# GIO.net
KiCad netlist of a schematic drawn in Altium Designer
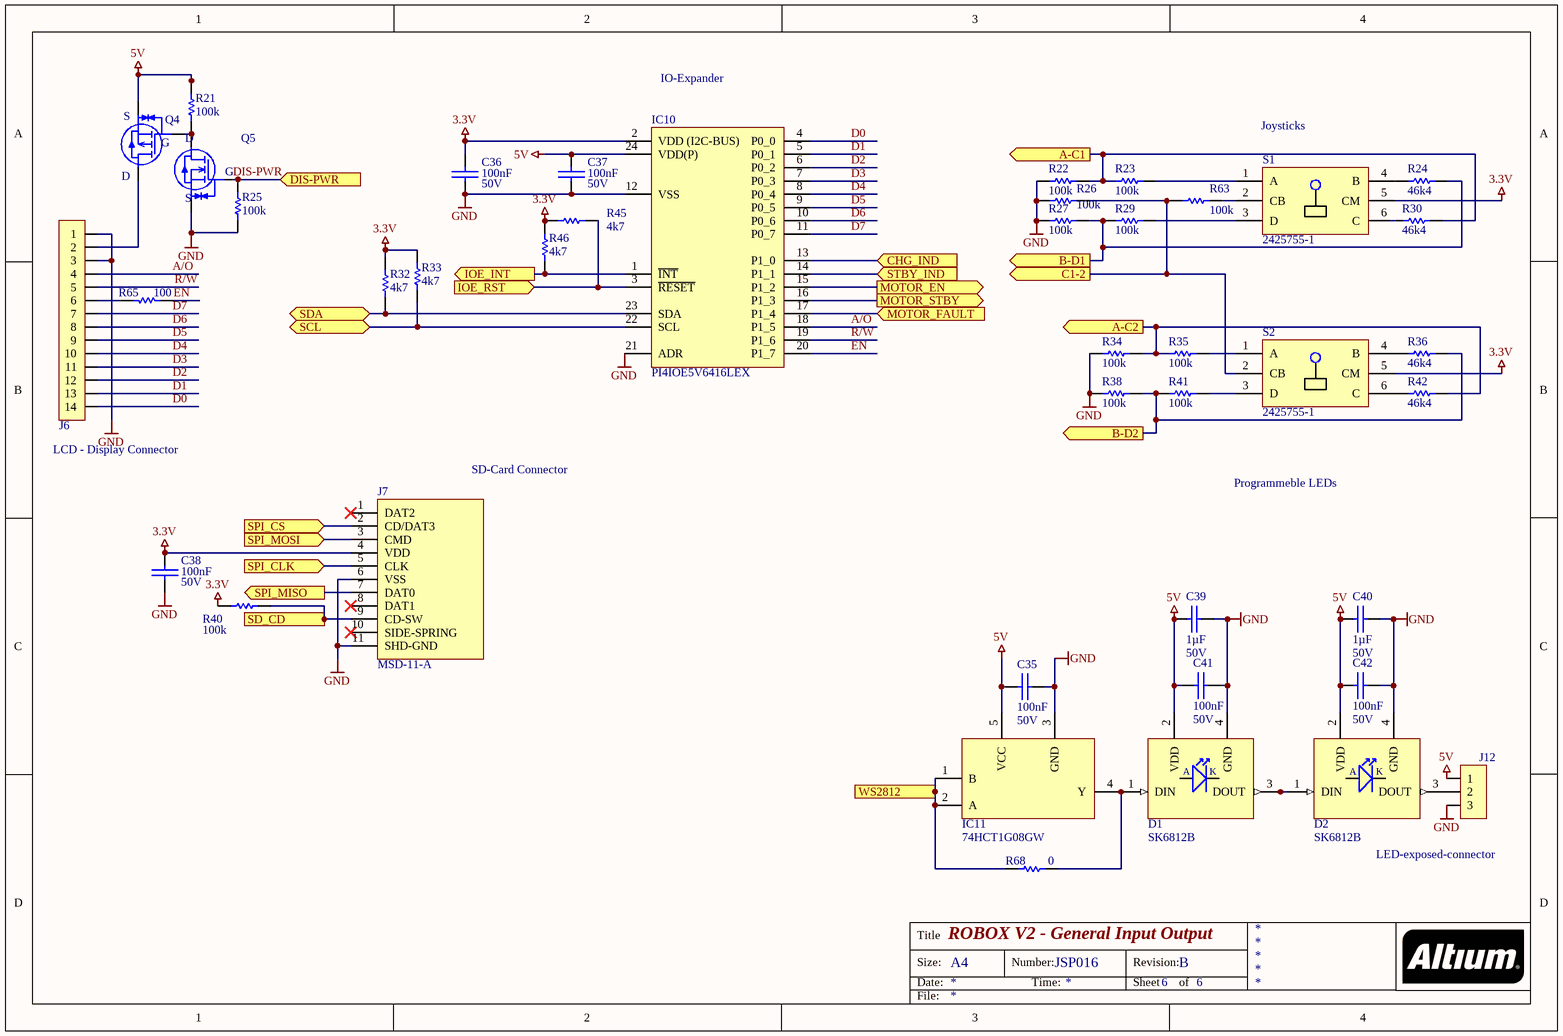
[diagram p0: GIO.SchDoc]

(export (version "E")
  (design (tool "Eeschema 10.0.6"))
  (components
    (comp (ref "C35")
      (value "100nF")
      (footprint "TH5.08")
      (description "CAP CER TH 100nF X7R 50V")
      (fields
        (field (name "MANUFACTURER") "FH")
        (field (name "TOLERANCE") "10%")
        (field (name "VOLTAGE") "50V")
      )
      (libsource (lib "bond-altium-excell") (part "cap_non_pol"))
    )
    (comp (ref "C36")
      (value "100nF")
      (footprint "C0402")
      (description "CAP CER 0.1UF 50V X5R 0402")
      (fields
        (field (name "MANUFACTURER") "Murata Electronics")
        (field (name "TOLERANCE") "5%")
        (field (name "VOLTAGE") "50V")
      )
      (libsource (lib "bond-altium-excell") (part "cap_non_pol"))
    )
    (comp (ref "C37")
      (value "100nF")
      (footprint "C0402")
      (description "CAP CER 0.1UF 50V X5R 0402")
      (fields
        (field (name "MANUFACTURER") "Murata Electronics")
        (field (name "TOLERANCE") "5%")
        (field (name "VOLTAGE") "50V")
      )
      (libsource (lib "bond-altium-excell") (part "cap_non_pol"))
    )
    (comp (ref "C38")
      (value "100nF")
      (footprint "C0402")
      (description "CAP CER 0.1UF 50V X5R 0402")
      (fields
        (field (name "MANUFACTURER") "Murata Electronics")
        (field (name "TOLERANCE") "5%")
        (field (name "VOLTAGE") "50V")
      )
      (libsource (lib "bond-altium-excell") (part "cap_non_pol"))
    )
    (comp (ref "C39")
      (value "1µF")
      (footprint "TH5.08")
      (description "CAP CER TH 1µF X7R 50V")
      (fields
        (field (name "MANUFACTURER") "Dersonic")
        (field (name "TOLERANCE") "20%")
        (field (name "VOLTAGE") "50V")
      )
      (libsource (lib "bond-altium-excell") (part "cap_non_pol"))
    )
    (comp (ref "C40")
      (value "1µF")
      (footprint "TH5.08")
      (description "CAP CER TH 1µF X7R 50V")
      (fields
        (field (name "MANUFACTURER") "Dersonic")
        (field (name "TOLERANCE") "20%")
        (field (name "VOLTAGE") "50V")
      )
      (libsource (lib "bond-altium-excell") (part "cap_non_pol"))
    )
    (comp (ref "C41")
      (value "100nF")
      (footprint "TH5.08")
      (description "CAP CER TH 100nF X7R 50V")
      (fields
        (field (name "MANUFACTURER") "FH")
        (field (name "TOLERANCE") "10%")
        (field (name "VOLTAGE") "50V")
      )
      (libsource (lib "bond-altium-excell") (part "cap_non_pol"))
    )
    (comp (ref "C42")
      (value "100nF")
      (footprint "TH5.08")
      (description "CAP CER TH 100nF X7R 50V")
      (fields
        (field (name "MANUFACTURER") "FH")
        (field (name "TOLERANCE") "10%")
        (field (name "VOLTAGE") "50V")
      )
      (libsource (lib "bond-altium-excell") (part "cap_non_pol"))
    )
    (comp (ref "D1")
      (value "SK6812B")
      (footprint "SK6812B")
      (description "ADDRESS LED DISCRETE RGB 4X2MM")
      (fields (field (name "MANUFACTURER") "Adafruit Industries LLC"))
      (libsource (lib "bond-altium-excell") (part "SK6812B"))
    )
    (comp (ref "D2")
      (value "SK6812B")
      (footprint "SK6812B")
      (description "ADDRESS LED DISCRETE RGB 4X2MM")
      (fields (field (name "MANUFACTURER") "Adafruit Industries LLC"))
      (libsource (lib "bond-altium-excell") (part "SK6812B"))
    )
    (comp (ref "IC10")
      (value "PI4IOE5V6416LEX")
      (footprint "TSSOP-24")
      (description "IC XPNDR 400KHZ I2C 24TSSOP")
      (fields (field (name "MANUFACTURER") "Diodes Incorporated"))
      (libsource (lib "bond-altium-excell") (part "PI4IOE5V6416LEX"))
    )
    (comp (ref "IC11")
      (value "74HCT1G08GW")
      (footprint "TSSOP-5")
      (description "IC GATE AND 1CH 2-INP 5TSSOP")
      (fields (field (name "MANUFACTURER") "Nexperia USA Inc."))
      (libsource (lib "bond-altium-excell") (part "74HCT1G08GW"))
    )
    (comp (ref "J6")
      (value "Pin-14")
      (footprint "HLW14S-2C7LF")
      (description "CONN FFC FPC VERT 14POS 1MM PCB")
      (fields (field (name "MANUFACTURER") "Amphenol ICC (FCI)"))
      (libsource (lib "bond-altium-excell") (part "Pin-14"))
    )
    (comp (ref "J7")
      (value "MSD-11-A")
      (footprint "MSD-11-A")
      (description "MICRO SD CARD CONNECTOR, 8 POSIT")
      (fields (field (name "MANUFACTURER") "CUI Devices"))
      (libsource (lib "bond-altium-excell") (part "MSD-11-A"))
    )
    (comp (ref "J12")
      (value "Pin-3")
      (footprint "3-PIN-EMPTY")
      (description "CONN TH solder pad")
      (libsource (lib "bond-altium-excell") (part "Pin-3"))
    )
    (comp (ref "Q4")
      (value "P_CH_MOSFET2")
      (footprint "SOT-323")
      (description "MOSFET P-CH 20V 820MA SOT323")
      (fields (field (name "MANUFACTURER") "Diodes Incorporated"))
      (libsource (lib "bond-altium-excell") (part "P_CH_MOSFET2"))
    )
    (comp (ref "Q5")
      (value "N_CH_MOSFET")
      (footprint "SOT-23(-3)")
      (description "MOSFET N-CH 100V 170MA SOT23-3")
      (fields (field (name "MANUFACTURER") "Diodes Incorporated"))
      (libsource (lib "bond-altium-excell") (part "N_CH_MOSFET"))
    )
    (comp (ref "R21")
      (value "100k")
      (footprint "R0402")
      (description "RES SMD 100K OHM 1% 1/10W 0402")
      (fields (field (name "MANUFACTURER") "Panasonic Electronic Components") (field (name "TOLERANCE") "1%"))
      (libsource (lib "bond-altium-excell") (part "resistor"))
    )
    (comp (ref "R22")
      (value "100k")
      (footprint "R0402")
      (description "RES SMD 100K OHM 1% 1/10W 0402")
      (fields (field (name "MANUFACTURER") "Panasonic Electronic Components") (field (name "TOLERANCE") "1%"))
      (libsource (lib "bond-altium-excell") (part "resistor"))
    )
    (comp (ref "R23")
      (value "100k")
      (footprint "R0402")
      (description "RES SMD 100K OHM 1% 1/10W 0402")
      (fields (field (name "MANUFACTURER") "Panasonic Electronic Components") (field (name "TOLERANCE") "1%"))
      (libsource (lib "bond-altium-excell") (part "resistor"))
    )
    (comp (ref "R24")
      (value "46k4")
      (footprint "R0402")
      (description "RES SMD 46.4K OHM 1% 1/16W 0402")
      (fields (field (name "MANUFACTURER") "Yageo") (field (name "TOLERANCE") "1%"))
      (libsource (lib "bond-altium-excell") (part "resistor"))
    )
    (comp (ref "R25")
      (value "100k")
      (footprint "R0402")
      (description "RES SMD 100K OHM 1% 1/10W 0402")
      (fields (field (name "MANUFACTURER") "Panasonic Electronic Components") (field (name "TOLERANCE") "1%"))
      (libsource (lib "bond-altium-excell") (part "resistor"))
    )
    (comp (ref "R26")
      (value "100k")
      (footprint "R0402")
      (description "RES SMD 100K OHM 1% 1/10W 0402")
      (fields (field (name "MANUFACTURER") "Panasonic Electronic Components") (field (name "TOLERANCE") "1%"))
      (libsource (lib "bond-altium-excell") (part "resistor"))
    )
    (comp (ref "R27")
      (value "100k")
      (footprint "R0402")
      (description "RES SMD 100K OHM 1% 1/10W 0402")
      (fields (field (name "MANUFACTURER") "Panasonic Electronic Components") (field (name "TOLERANCE") "1%"))
      (libsource (lib "bond-altium-excell") (part "resistor"))
    )
    (comp (ref "R29")
      (value "100k")
      (footprint "R0402")
      (description "RES SMD 100K OHM 1% 1/10W 0402")
      (fields (field (name "MANUFACTURER") "Panasonic Electronic Components") (field (name "TOLERANCE") "1%"))
      (libsource (lib "bond-altium-excell") (part "resistor"))
    )
    (comp (ref "R30")
      (value "46k4")
      (footprint "R0402")
      (description "RES SMD 46.4K OHM 1% 1/16W 0402")
      (fields (field (name "MANUFACTURER") "Yageo") (field (name "TOLERANCE") "1%"))
      (libsource (lib "bond-altium-excell") (part "resistor"))
    )
    (comp (ref "R32")
      (value "4k7")
      (footprint "R0402")
      (description "RES SMD 4.7K OHM 1% 1/10W 0402")
      (fields (field (name "MANUFACTURER") "Panasonic Electronic Components") (field (name "TOLERANCE") "1%"))
      (libsource (lib "bond-altium-excell") (part "resistor"))
    )
    (comp (ref "R33")
      (value "4k7")
      (footprint "R0402")
      (description "RES SMD 4.7K OHM 1% 1/10W 0402")
      (fields (field (name "MANUFACTURER") "Panasonic Electronic Components") (field (name "TOLERANCE") "1%"))
      (libsource (lib "bond-altium-excell") (part "resistor"))
    )
    (comp (ref "R34")
      (value "100k")
      (footprint "R0402")
      (description "RES SMD 100K OHM 1% 1/10W 0402")
      (fields (field (name "MANUFACTURER") "Panasonic Electronic Components") (field (name "TOLERANCE") "1%"))
      (libsource (lib "bond-altium-excell") (part "resistor"))
    )
    (comp (ref "R35")
      (value "100k")
      (footprint "R0402")
      (description "RES SMD 100K OHM 1% 1/10W 0402")
      (fields (field (name "MANUFACTURER") "Panasonic Electronic Components") (field (name "TOLERANCE") "1%"))
      (libsource (lib "bond-altium-excell") (part "resistor"))
    )
    (comp (ref "R36")
      (value "46k4")
      (footprint "R0402")
      (description "RES SMD 46.4K OHM 1% 1/16W 0402")
      (fields (field (name "MANUFACTURER") "Yageo") (field (name "TOLERANCE") "1%"))
      (libsource (lib "bond-altium-excell") (part "resistor"))
    )
    (comp (ref "R38")
      (value "100k")
      (footprint "R0402")
      (description "RES SMD 100K OHM 1% 1/10W 0402")
      (fields (field (name "MANUFACTURER") "Panasonic Electronic Components") (field (name "TOLERANCE") "1%"))
      (libsource (lib "bond-altium-excell") (part "resistor"))
    )
    (comp (ref "R40")
      (value "100k")
      (footprint "R0402")
      (description "RES SMD 100K OHM 1% 1/10W 0402")
      (fields (field (name "MANUFACTURER") "Panasonic Electronic Components") (field (name "TOLERANCE") "1%"))
      (libsource (lib "bond-altium-excell") (part "resistor"))
    )
    (comp (ref "R41")
      (value "100k")
      (footprint "R0402")
      (description "RES SMD 100K OHM 1% 1/10W 0402")
      (fields (field (name "MANUFACTURER") "Panasonic Electronic Components") (field (name "TOLERANCE") "1%"))
      (libsource (lib "bond-altium-excell") (part "resistor"))
    )
    (comp (ref "R42")
      (value "46k4")
      (footprint "R0402")
      (description "RES SMD 46.4K OHM 1% 1/16W 0402")
      (fields (field (name "MANUFACTURER") "Yageo") (field (name "TOLERANCE") "1%"))
      (libsource (lib "bond-altium-excell") (part "resistor"))
    )
    (comp (ref "R45")
      (value "4k7")
      (footprint "R0402")
      (description "RES SMD 4.7K OHM 1% 1/10W 0402")
      (fields (field (name "MANUFACTURER") "Panasonic Electronic Components") (field (name "TOLERANCE") "1%"))
      (libsource (lib "bond-altium-excell") (part "resistor"))
    )
    (comp (ref "R46")
      (value "4k7")
      (footprint "R0402")
      (description "RES SMD 4.7K OHM 1% 1/10W 0402")
      (fields (field (name "MANUFACTURER") "Panasonic Electronic Components") (field (name "TOLERANCE") "1%"))
      (libsource (lib "bond-altium-excell") (part "resistor"))
    )
    (comp (ref "R63")
      (value "100k")
      (footprint "R0402")
      (description "RES SMD 100K OHM 1% 1/10W 0402")
      (fields (field (name "MANUFACTURER") "Panasonic Electronic Components") (field (name "TOLERANCE") "1%"))
      (libsource (lib "bond-altium-excell") (part "resistor"))
    )
    (comp (ref "R65")
      (value "100")
      (footprint "R0402")
      (description "RES SMD 100 OHM 1% 1/5W 0402")
      (fields (field (name "MANUFACTURER") "Vishay Dale") (field (name "TOLERANCE") "1%"))
      (libsource (lib "bond-altium-excell") (part "resistor"))
    )
    (comp (ref "R68")
      (value "0")
      (footprint "R0402")
      (description "RES SMD 0 OHM JUMPER 1/10W 0402")
      (fields (field (name "MANUFACTURER") "Panasonic Electronic Components") (field (name "TOLERANCE") "1%"))
      (libsource (lib "bond-altium-excell") (part "resistor"))
    )
    (comp (ref "S1")
      (value "2425755-1")
      (footprint "2425755-1")
      (description "SWITCH NAVIGATION DGTL 50MA 12V")
      (fields (field (name "MANUFACTURER") "TE Connectivity"))
      (libsource (lib "bond-altium-excell") (part "2425755-1"))
    )
    (comp (ref "S2")
      (value "2425755-1")
      (footprint "2425755-1")
      (description "SWITCH NAVIGATION DGTL 50MA 12V")
      (fields (field (name "MANUFACTURER") "TE Connectivity"))
      (libsource (lib "bond-altium-excell") (part "2425755-1"))
    )
  )
  (nets
    (net (code "1") (name "/A-C1") (class "Default")
      (node (ref "R22") (pin "1") (pinfunction "1_1") (pintype "passive"))
      (node (ref "R23") (pin "2") (pinfunction "2_2") (pintype "passive"))
      (node (ref "R30") (pin "1") (pinfunction "1_1") (pintype "passive"))
    )
    (net (code "2") (name "/A-C2") (class "Default")
      (node (ref "R34") (pin "1") (pinfunction "1_1") (pintype "passive"))
      (node (ref "R35") (pin "2") (pinfunction "2_2") (pintype "passive"))
      (node (ref "R42") (pin "1") (pinfunction "1_1") (pintype "passive"))
    )
    (net (code "3") (name "/A{slash}O") (class "Default")
      (node (ref "IC10") (pin "18") (pinfunction "P1_5_18") (pintype "passive"))
      (node (ref "J6") (pin "4") (pinfunction "4_4") (pintype "passive"))
    )
    (net (code "4") (name "/B-D1") (class "Default")
      (node (ref "R24") (pin "1") (pinfunction "1_1") (pintype "passive"))
      (node (ref "R27") (pin "1") (pinfunction "1_1") (pintype "passive"))
      (node (ref "R29") (pin "2") (pinfunction "2_2") (pintype "passive"))
    )
    (net (code "5") (name "/B-D2") (class "Default")
      (node (ref "R36") (pin "1") (pinfunction "1_1") (pintype "passive"))
      (node (ref "R38") (pin "1") (pinfunction "1_1") (pintype "passive"))
      (node (ref "R41") (pin "2") (pinfunction "2_2") (pintype "passive"))
    )
    (net (code "6") (name "/C1-2") (class "Default")
      (node (ref "R26") (pin "1") (pinfunction "1_1") (pintype "passive"))
      (node (ref "R63") (pin "2") (pinfunction "2_2") (pintype "passive"))
      (node (ref "S2") (pin "2") (pinfunction "CB_2") (pintype "passive"))
    )
    (net (code "7") (name "/CHG_IND") (class "Default")
      (node (ref "IC10") (pin "13") (pinfunction "P1_0_13") (pintype "passive"))
    )
    (net (code "8") (name "/D0") (class "Default")
      (node (ref "IC10") (pin "4") (pinfunction "P0_0_4") (pintype "passive"))
      (node (ref "J6") (pin "14") (pinfunction "14_14") (pintype "passive"))
    )
    (net (code "9") (name "/D1") (class "Default")
      (node (ref "IC10") (pin "5") (pinfunction "P0_1_5") (pintype "passive"))
      (node (ref "J6") (pin "13") (pinfunction "13_13") (pintype "passive"))
    )
    (net (code "10") (name "/D2") (class "Default")
      (node (ref "IC10") (pin "6") (pinfunction "P0_2_6") (pintype "passive"))
      (node (ref "J6") (pin "12") (pinfunction "12_12") (pintype "passive"))
    )
    (net (code "11") (name "/D3") (class "Default")
      (node (ref "IC10") (pin "7") (pinfunction "P0_3_7") (pintype "passive"))
      (node (ref "J6") (pin "11") (pinfunction "11_11") (pintype "passive"))
    )
    (net (code "12") (name "/D4") (class "Default")
      (node (ref "IC10") (pin "8") (pinfunction "P0_4_8") (pintype "passive"))
      (node (ref "J6") (pin "10") (pinfunction "10_10") (pintype "passive"))
    )
    (net (code "13") (name "/D5") (class "Default")
      (node (ref "IC10") (pin "9") (pinfunction "P0_5_9") (pintype "passive"))
      (node (ref "J6") (pin "9") (pinfunction "9_9") (pintype "passive"))
    )
    (net (code "14") (name "/D6") (class "Default")
      (node (ref "IC10") (pin "10") (pinfunction "P0_6_10") (pintype "passive"))
      (node (ref "J6") (pin "8") (pinfunction "8_8") (pintype "passive"))
    )
    (net (code "15") (name "/D7") (class "Default")
      (node (ref "IC10") (pin "11") (pinfunction "P0_7_11") (pintype "passive"))
      (node (ref "J6") (pin "7") (pinfunction "7_7") (pintype "passive"))
    )
    (net (code "16") (name "/DIS-PWR") (class "Default")
      (node (ref "Q5") (pin "1") (pinfunction "G_1") (pintype "passive"))
      (node (ref "R25") (pin "1") (pinfunction "1_1") (pintype "passive"))
    )
    (net (code "17") (name "/EN") (class "Default")
      (node (ref "IC10") (pin "20") (pinfunction "P1_7_20") (pintype "passive"))
      (node (ref "R65") (pin "2") (pinfunction "2_2") (pintype "passive"))
    )
    (net (code "18") (name "/IOE_INT") (class "Default")
      (node (ref "IC10") (pin "1") (pinfunction "~{INT}_1") (pintype "passive"))
      (node (ref "R46") (pin "1") (pinfunction "1_1") (pintype "passive"))
    )
    (net (code "19") (name "/IOE_RST") (class "Default")
      (node (ref "IC10") (pin "3") (pinfunction "~{RESET}_3") (pintype "passive"))
      (node (ref "R45") (pin "1") (pinfunction "1_1") (pintype "passive"))
    )
    (net (code "20") (name "/MOTOR_EN") (class "Default")
      (node (ref "IC10") (pin "15") (pinfunction "P1_2_15") (pintype "passive"))
    )
    (net (code "21") (name "/MOTOR_FAULT") (class "Default")
      (node (ref "IC10") (pin "17") (pinfunction "P1_4_17") (pintype "passive"))
    )
    (net (code "22") (name "/MOTOR_STBY") (class "Default")
      (node (ref "IC10") (pin "16") (pinfunction "P1_3_16") (pintype "passive"))
    )
    (net (code "23") (name "/R{slash}W") (class "Default")
      (node (ref "IC10") (pin "19") (pinfunction "P1_6_19") (pintype "passive"))
      (node (ref "J6") (pin "5") (pinfunction "5_5") (pintype "passive"))
    )
    (net (code "24") (name "/SCL") (class "Default")
      (node (ref "IC10") (pin "22") (pinfunction "SCL_22") (pintype "passive"))
      (node (ref "R33") (pin "1") (pinfunction "1_1") (pintype "passive"))
    )
    (net (code "25") (name "/SDA") (class "Default")
      (node (ref "IC10") (pin "23") (pinfunction "SDA_23") (pintype "passive"))
      (node (ref "R32") (pin "1") (pinfunction "1_1") (pintype "passive"))
    )
    (net (code "26") (name "/SD_CD") (class "Default")
      (node (ref "J7") (pin "9") (pinfunction "CD-SW_9") (pintype "passive"))
      (node (ref "R40") (pin "1") (pinfunction "1_1") (pintype "passive"))
    )
    (net (code "27") (name "/SPI_CLK") (class "Default")
      (node (ref "J7") (pin "5") (pinfunction "CLK_5") (pintype "passive"))
    )
    (net (code "28") (name "/SPI_CS") (class "Default")
      (node (ref "J7") (pin "2") (pinfunction "CD/DAT3_2") (pintype "passive"))
    )
    (net (code "29") (name "/SPI_MISO") (class "Default")
      (node (ref "J7") (pin "7") (pinfunction "DAT0_7") (pintype "passive"))
    )
    (net (code "30") (name "/SPI_MOSI") (class "Default")
      (node (ref "J7") (pin "3") (pinfunction "CMD_3") (pintype "passive"))
    )
    (net (code "31") (name "/STBY_IND") (class "Default")
      (node (ref "IC10") (pin "14") (pinfunction "P1_1_14") (pintype "passive"))
    )
    (net (code "32") (name "/WS2812") (class "Default")
      (node (ref "IC11") (pin "1") (pinfunction "B_1") (pintype "passive"))
      (node (ref "IC11") (pin "2") (pinfunction "A_2") (pintype "passive"))
      (node (ref "R68") (pin "2") (pinfunction "2_2") (pintype "passive"))
    )
    (net (code "33") (name "3.3V") (class "Default")
      (node (ref "C36") (pin "2") (pinfunction "2_2") (pintype "passive"))
      (node (ref "C38") (pin "2") (pinfunction "2_2") (pintype "passive"))
      (node (ref "IC10") (pin "2") (pinfunction "VDD_(I2C-BUS)_2") (pintype "passive"))
      (node (ref "J7") (pin "4") (pinfunction "VDD_4") (pintype "passive"))
      (node (ref "R32") (pin "2") (pinfunction "2_2") (pintype "passive"))
      (node (ref "R33") (pin "2") (pinfunction "2_2") (pintype "passive"))
      (node (ref "R40") (pin "2") (pinfunction "2_2") (pintype "passive"))
      (node (ref "R45") (pin "2") (pinfunction "2_2") (pintype "passive"))
      (node (ref "R46") (pin "2") (pinfunction "2_2") (pintype "passive"))
      (node (ref "S1") (pin "5") (pinfunction "CM_5") (pintype "passive"))
      (node (ref "S2") (pin "5") (pinfunction "CM_5") (pintype "passive"))
    )
    (net (code "34") (name "5V") (class "Default")
      (node (ref "C35") (pin "1") (pinfunction "1_1") (pintype "passive"))
      (node (ref "C37") (pin "2") (pinfunction "2_2") (pintype "passive"))
      (node (ref "C39") (pin "2") (pinfunction "2_2") (pintype "passive"))
      (node (ref "C40") (pin "2") (pinfunction "2_2") (pintype "passive"))
      (node (ref "C41") (pin "1") (pinfunction "1_1") (pintype "passive"))
      (node (ref "C42") (pin "1") (pinfunction "1_1") (pintype "passive"))
      (node (ref "D1") (pin "2") (pinfunction "VDD_2") (pintype "power_in"))
      (node (ref "D2") (pin "2") (pinfunction "VDD_2") (pintype "power_in"))
      (node (ref "IC10") (pin "24") (pinfunction "VDD(P)_24") (pintype "passive"))
      (node (ref "IC11") (pin "5") (pinfunction "VCC_5") (pintype "passive"))
      (node (ref "J12") (pin "1") (pinfunction "1_1") (pintype "passive"))
      (node (ref "Q4") (pin "S") (pinfunction "S_S") (pintype "passive"))
      (node (ref "R21") (pin "1") (pinfunction "1_1") (pintype "passive"))
    )
    (net (code "35") (name "GND") (class "Default")
      (node (ref "C35") (pin "2") (pinfunction "2_2") (pintype "passive"))
      (node (ref "C36") (pin "1") (pinfunction "1_1") (pintype "passive"))
      (node (ref "C37") (pin "1") (pinfunction "1_1") (pintype "passive"))
      (node (ref "C38") (pin "1") (pinfunction "1_1") (pintype "passive"))
      (node (ref "C39") (pin "1") (pinfunction "1_1") (pintype "passive"))
      (node (ref "C40") (pin "1") (pinfunction "1_1") (pintype "passive"))
      (node (ref "C41") (pin "2") (pinfunction "2_2") (pintype "passive"))
      (node (ref "C42") (pin "2") (pinfunction "2_2") (pintype "passive"))
      (node (ref "D1") (pin "4") (pinfunction "GND_4") (pintype "power_in"))
      (node (ref "D2") (pin "4") (pinfunction "GND_4") (pintype "power_in"))
      (node (ref "IC10") (pin "12") (pinfunction "VSS_12") (pintype "passive"))
      (node (ref "IC10") (pin "21") (pinfunction "ADR_21") (pintype "passive"))
      (node (ref "IC11") (pin "3") (pinfunction "GND_3") (pintype "passive"))
      (node (ref "J12") (pin "3") (pinfunction "3_3") (pintype "passive"))
      (node (ref "J6") (pin "1") (pinfunction "1_1") (pintype "passive"))
      (node (ref "J6") (pin "3") (pinfunction "3_3") (pintype "passive"))
      (node (ref "J7") (pin "11") (pinfunction "SHD-GND_11") (pintype "passive"))
      (node (ref "J7") (pin "6") (pinfunction "VSS_6") (pintype "passive"))
      (node (ref "Q5") (pin "2") (pinfunction "S_2") (pintype "passive"))
      (node (ref "R22") (pin "2") (pinfunction "2_2") (pintype "passive"))
      (node (ref "R25") (pin "2") (pinfunction "2_2") (pintype "passive"))
      (node (ref "R26") (pin "2") (pinfunction "2_2") (pintype "passive"))
      (node (ref "R27") (pin "2") (pinfunction "2_2") (pintype "passive"))
      (node (ref "R34") (pin "2") (pinfunction "2_2") (pintype "passive"))
      (node (ref "R38") (pin "2") (pinfunction "2_2") (pintype "passive"))
    )
    (net (code "36") (name "Net-(D1-DIN)") (class "Default")
      (node (ref "D1") (pin "1") (pinfunction "DIN_1") (pintype "input"))
      (node (ref "IC11") (pin "4") (pinfunction "Y_4") (pintype "passive"))
      (node (ref "R68") (pin "1") (pinfunction "1_1") (pintype "passive"))
    )
    (net (code "37") (name "Net-(D1-DOUT)") (class "Default")
      (node (ref "D1") (pin "3") (pinfunction "DOUT_3") (pintype "output"))
      (node (ref "D2") (pin "1") (pinfunction "DIN_1") (pintype "input"))
    )
    (net (code "38") (name "Net-(D2-DOUT)") (class "Default")
      (node (ref "D2") (pin "3") (pinfunction "DOUT_3") (pintype "output"))
      (node (ref "J12") (pin "2") (pinfunction "2_2") (pintype "passive"))
    )
    (net (code "39") (name "Net-(J6-Pad2)") (class "Default")
      (node (ref "J6") (pin "2") (pinfunction "2_2") (pintype "passive"))
      (node (ref "Q4") (pin "D") (pinfunction "D_D") (pintype "passive"))
    )
    (net (code "40") (name "Net-(J6-Pad6)") (class "Default")
      (node (ref "J6") (pin "6") (pinfunction "6_6") (pintype "passive"))
      (node (ref "R65") (pin "1") (pinfunction "1_1") (pintype "passive"))
    )
    (net (code "41") (name "Net-(Q5-D)") (class "Default")
      (node (ref "Q4") (pin "G") (pinfunction "G_G") (pintype "passive"))
      (node (ref "Q5") (pin "3") (pinfunction "D_3") (pintype "passive"))
      (node (ref "R21") (pin "2") (pinfunction "2_2") (pintype "passive"))
    )
    (net (code "42") (name "Net-(S1-A)") (class "Default")
      (node (ref "R23") (pin "1") (pinfunction "1_1") (pintype "passive"))
      (node (ref "S1") (pin "1") (pinfunction "A_1") (pintype "passive"))
    )
    (net (code "43") (name "Net-(S1-B)") (class "Default")
      (node (ref "R24") (pin "2") (pinfunction "2_2") (pintype "passive"))
      (node (ref "S1") (pin "4") (pinfunction "B_4") (pintype "passive"))
    )
    (net (code "44") (name "Net-(S1-C)") (class "Default")
      (node (ref "R30") (pin "2") (pinfunction "2_2") (pintype "passive"))
      (node (ref "S1") (pin "6") (pinfunction "C_6") (pintype "passive"))
    )
    (net (code "45") (name "Net-(S1-CB)") (class "Default")
      (node (ref "R63") (pin "1") (pinfunction "1_1") (pintype "passive"))
      (node (ref "S1") (pin "2") (pinfunction "CB_2") (pintype "passive"))
    )
    (net (code "46") (name "Net-(S1-D)") (class "Default")
      (node (ref "R29") (pin "1") (pinfunction "1_1") (pintype "passive"))
      (node (ref "S1") (pin "3") (pinfunction "D_3") (pintype "passive"))
    )
    (net (code "47") (name "Net-(S2-A)") (class "Default")
      (node (ref "R35") (pin "1") (pinfunction "1_1") (pintype "passive"))
      (node (ref "S2") (pin "1") (pinfunction "A_1") (pintype "passive"))
    )
    (net (code "48") (name "Net-(S2-B)") (class "Default")
      (node (ref "R36") (pin "2") (pinfunction "2_2") (pintype "passive"))
      (node (ref "S2") (pin "4") (pinfunction "B_4") (pintype "passive"))
    )
    (net (code "49") (name "Net-(S2-C)") (class "Default")
      (node (ref "R42") (pin "2") (pinfunction "2_2") (pintype "passive"))
      (node (ref "S2") (pin "6") (pinfunction "C_6") (pintype "passive"))
    )
    (net (code "50") (name "Net-(S2-D)") (class "Default")
      (node (ref "R41") (pin "1") (pinfunction "1_1") (pintype "passive"))
      (node (ref "S2") (pin "3") (pinfunction "D_3") (pintype "passive"))
    )
    (net (code "51") (name "unconnected-(J7-DAT1-Pad8)") (class "Default")
      (node (ref "J7") (pin "8") (pinfunction "DAT1_8") (pintype "passive+no_connect"))
    )
    (net (code "52") (name "unconnected-(J7-DAT2-Pad1)") (class "Default")
      (node (ref "J7") (pin "1") (pinfunction "DAT2_1") (pintype "passive+no_connect"))
    )
    (net (code "53") (name "unconnected-(J7-SIDE-SPRING-Pad10)") (class "Default")
      (node (ref "J7") (pin "10") (pinfunction "SIDE-SPRING_10") (pintype "passive+no_connect"))
    )
  )
)
